# Peripherals_-_USB.net
KiCad netlist of a schematic drawn in Altium Designer
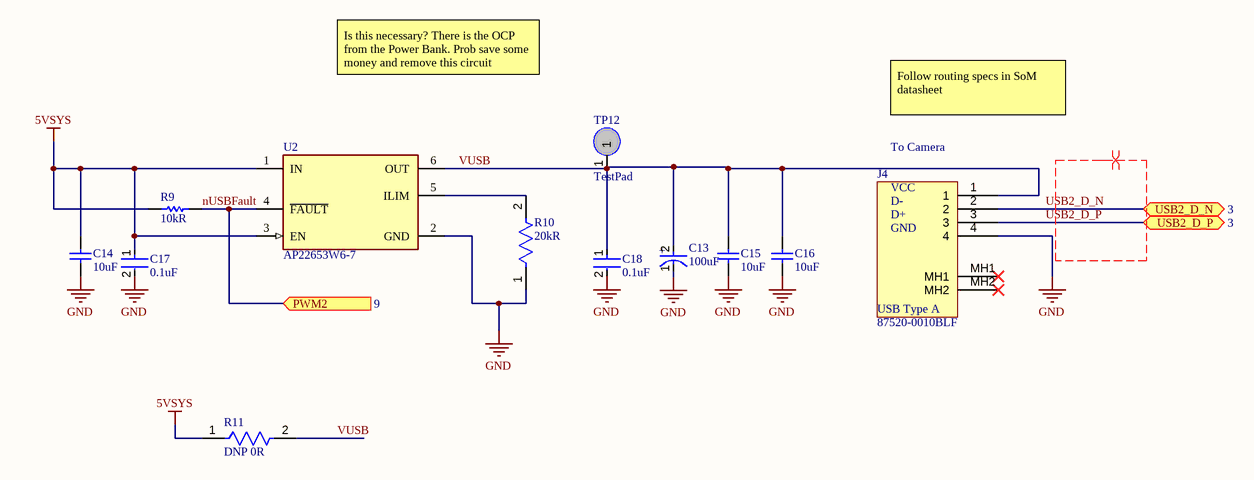
[diagram p0: Peripherals - USB.SchDoc]

(export (version "E")
  (design (tool "Eeschema 10.0.6"))
  (components
    (comp (ref "C13")
      (value "100uF")
      (footprint "FP-UWX1E101MCL1GB-MFG")
      (description "UWX1E101MCL1GB\r\nCAP ALUM 100UF 20% 25V SMD")
      (fields (field (name "TOLERANCE") "20%") (field (name "VOLTAGE") "25V"))
      (libsource (lib "Altium Content Vault") (part "203bc49f2ac43e59fd269a8c329ed05"))
    )
    (comp (ref "C14")
      (value "10uF")
      (footprint "CAPC2013X145X20ML20")
      (fields
        (field (name "MANUFACTURER") "TDK")
        (field (name "TOLERANCE") "±10%")
        (field (name "PCN PART NUMBER") "MLCCPartNumberChange30/Nov/2012")
      )
      (libsource (lib "Altium Content Vault") (part "CAP-NP-2"))
    )
    (comp (ref "C15")
      (value "10uF")
      (footprint "CAPC2013X145X20ML20")
      (fields
        (field (name "MANUFACTURER") "TDK")
        (field (name "TOLERANCE") "±10%")
        (field (name "PCN PART NUMBER") "MLCCPartNumberChange30/Nov/2012")
      )
      (libsource (lib "Altium Content Vault") (part "CAP-NP-2"))
    )
    (comp (ref "C16")
      (value "10uF")
      (footprint "CAPC2013X145X20ML20")
      (fields
        (field (name "MANUFACTURER") "TDK")
        (field (name "TOLERANCE") "±10%")
        (field (name "PCN PART NUMBER") "MLCCPartNumberChange30/Nov/2012")
      )
      (libsource (lib "Altium Content Vault") (part "CAP-NP-2"))
    )
    (comp (ref "C17")
      (value "0.1uF")
      (footprint "FP-C0603-CJ-MFG")
      (description "C0603X104K5RACTU CAP CER 0.1UF 50V X7R 0603")
      (fields (field (name "MANUFACTURER PART NUMBER") "C0603X104K5RACTU") (field (name "VOLTAGE") "50V"))
      (libsource (lib "Altium Content Vault") (part "11868f565c42a9108669ba33697ecf6"))
    )
    (comp (ref "C18")
      (value "0.1uF")
      (footprint "FP-C0603-CJ-MFG")
      (description "C0603X104K5RACTU CAP CER 0.1UF 50V X7R 0603")
      (fields (field (name "MANUFACTURER PART NUMBER") "C0603X104K5RACTU") (field (name "VOLTAGE") "50V"))
      (libsource (lib "Altium Content Vault") (part "11868f565c42a9108669ba33697ecf6"))
    )
    (comp (ref "J4")
      (value "87520-0010BLF")
      (footprint "LayoutFootprintsGoogle:875200010BLF")
      (libsource (lib "SchemSymbolsGoogle") (part "87520-0010BLF"))
    )
    (comp (ref "R9")
      (value "10kR")
      (footprint "RESC2013X60X35NL10T20")
      (fields (field (name "MANUFACTURER") "Yageo"))
      (libsource (lib "Altium Content Vault") (part "RES-2"))
    )
    (comp (ref "R10")
      (value "20kR")
      (footprint "FP-CRCW0805-e3-MFG")
      (description "RES Thick Film, 20kΩ, 1%, 0.125W, 100ppm/°C, 0805")
      (fields (field (name "TOLERANCE") "1%"))
      (libsource (lib "Altium Content Vault") (part "1029c3af85768c4190bb7ad29bc67b5"))
    )
    (comp (ref "R11")
      (value "DNP 0R")
      (footprint "FP-RC1206-MFG")
      (description "RC1206JR-070RL RES SMD 0 OHM JUMPER 1/4W 1206")
      (fields
        (field (name "MANUFACTURER PART NUMBER") "RC1206JR-070RL")
        (field (name "MANUFACTURER") "YAGEO")
      )
      (libsource (lib "Altium Content Vault") (part "1029c3af85768c4190bb7ad29bc67b5"))
    )
    (comp (ref "TP12")
      (value "TestPad")
      (footprint "TestPad50mil")
      (libsource (lib "SchemSymbolsGoogle") (part "TestPad"))
    )
    (comp (ref "U2")
      (value "AP22653W6-7")
      (footprint "FP-SOT26-MFG")
      (description "LOAD SWITCH,SOT26,T&R,3K")
      (libsource (lib "Altium Content Vault") (part "bad2b8b447a47ab10bab651f807ccff"))
    )
  )
  (nets
    (net (code "1") (name "/USB2_D_N") (class "Default")
      (node (ref "J4") (pin "2") (pinfunction "2_2") (pintype "passive"))
    )
    (net (code "2") (name "/USB2_D_P") (class "Default")
      (node (ref "J4") (pin "3") (pinfunction "3_3") (pintype "passive"))
    )
    (net (code "3") (name "/VUSB") (class "Default")
      (node (ref "C13") (pin "2") (pinfunction "A_2") (pintype "passive"))
      (node (ref "C15") (pin "2") (pinfunction "2_2") (pintype "passive"))
      (node (ref "C16") (pin "2") (pinfunction "2_2") (pintype "passive"))
      (node (ref "C18") (pin "1") (pinfunction "1_1") (pintype "passive"))
      (node (ref "J4") (pin "1") (pinfunction "1_1") (pintype "passive"))
      (node (ref "R11") (pin "2") (pinfunction "2_2") (pintype "passive"))
      (node (ref "TP12") (pin "1") (pinfunction "1_1") (pintype "passive"))
      (node (ref "U2") (pin "6") (pinfunction "OUT_6") (pintype "passive"))
    )
    (net (code "4") (name "/nUSBFault") (class "Default")
      (node (ref "R9") (pin "1") (pinfunction "1_1") (pintype "passive"))
      (node (ref "U2") (pin "4") (pinfunction "~{FAULT}_4") (pintype "open_collector"))
    )
    (net (code "5") (name "5VSYS") (class "Default")
      (node (ref "C14") (pin "2") (pinfunction "2_2") (pintype "passive"))
      (node (ref "C17") (pin "1") (pinfunction "1_1") (pintype "passive"))
      (node (ref "R11") (pin "1") (pinfunction "1_1") (pintype "passive"))
      (node (ref "R9") (pin "2") (pinfunction "2_2") (pintype "passive"))
      (node (ref "U2") (pin "1") (pinfunction "IN_1") (pintype "power_in"))
      (node (ref "U2") (pin "3") (pinfunction "EN_3") (pintype "input"))
    )
    (net (code "6") (name "GND") (class "Default")
      (node (ref "C13") (pin "1") (pinfunction "C_1") (pintype "passive"))
      (node (ref "C14") (pin "1") (pinfunction "1_1") (pintype "passive"))
      (node (ref "C15") (pin "1") (pinfunction "1_1") (pintype "passive"))
      (node (ref "C16") (pin "1") (pinfunction "1_1") (pintype "passive"))
      (node (ref "C17") (pin "2") (pinfunction "2_2") (pintype "passive"))
      (node (ref "C18") (pin "2") (pinfunction "2_2") (pintype "passive"))
      (node (ref "J4") (pin "4") (pinfunction "4_4") (pintype "passive"))
      (node (ref "R10") (pin "1") (pinfunction "1_1") (pintype "passive"))
      (node (ref "U2") (pin "2") (pinfunction "GND_2") (pintype "power_in"))
    )
    (net (code "7") (name "Net-(U2-ILIM)") (class "Default")
      (node (ref "R10") (pin "2") (pinfunction "2_2") (pintype "passive"))
      (node (ref "U2") (pin "5") (pinfunction "ILIM_5") (pintype "passive"))
    )
    (net (code "8") (name "unconnected-(J4-PadMH1)") (class "Default")
      (node (ref "J4") (pin "MH1") (pinfunction "MH1_MH1") (pintype "passive+no_connect"))
    )
    (net (code "9") (name "unconnected-(J4-PadMH2)") (class "Default")
      (node (ref "J4") (pin "MH2") (pinfunction "MH2_MH2") (pintype "passive+no_connect"))
    )
  )
)
